# transboard.net
KiCad netlist of a schematic drawn in Altium Designer
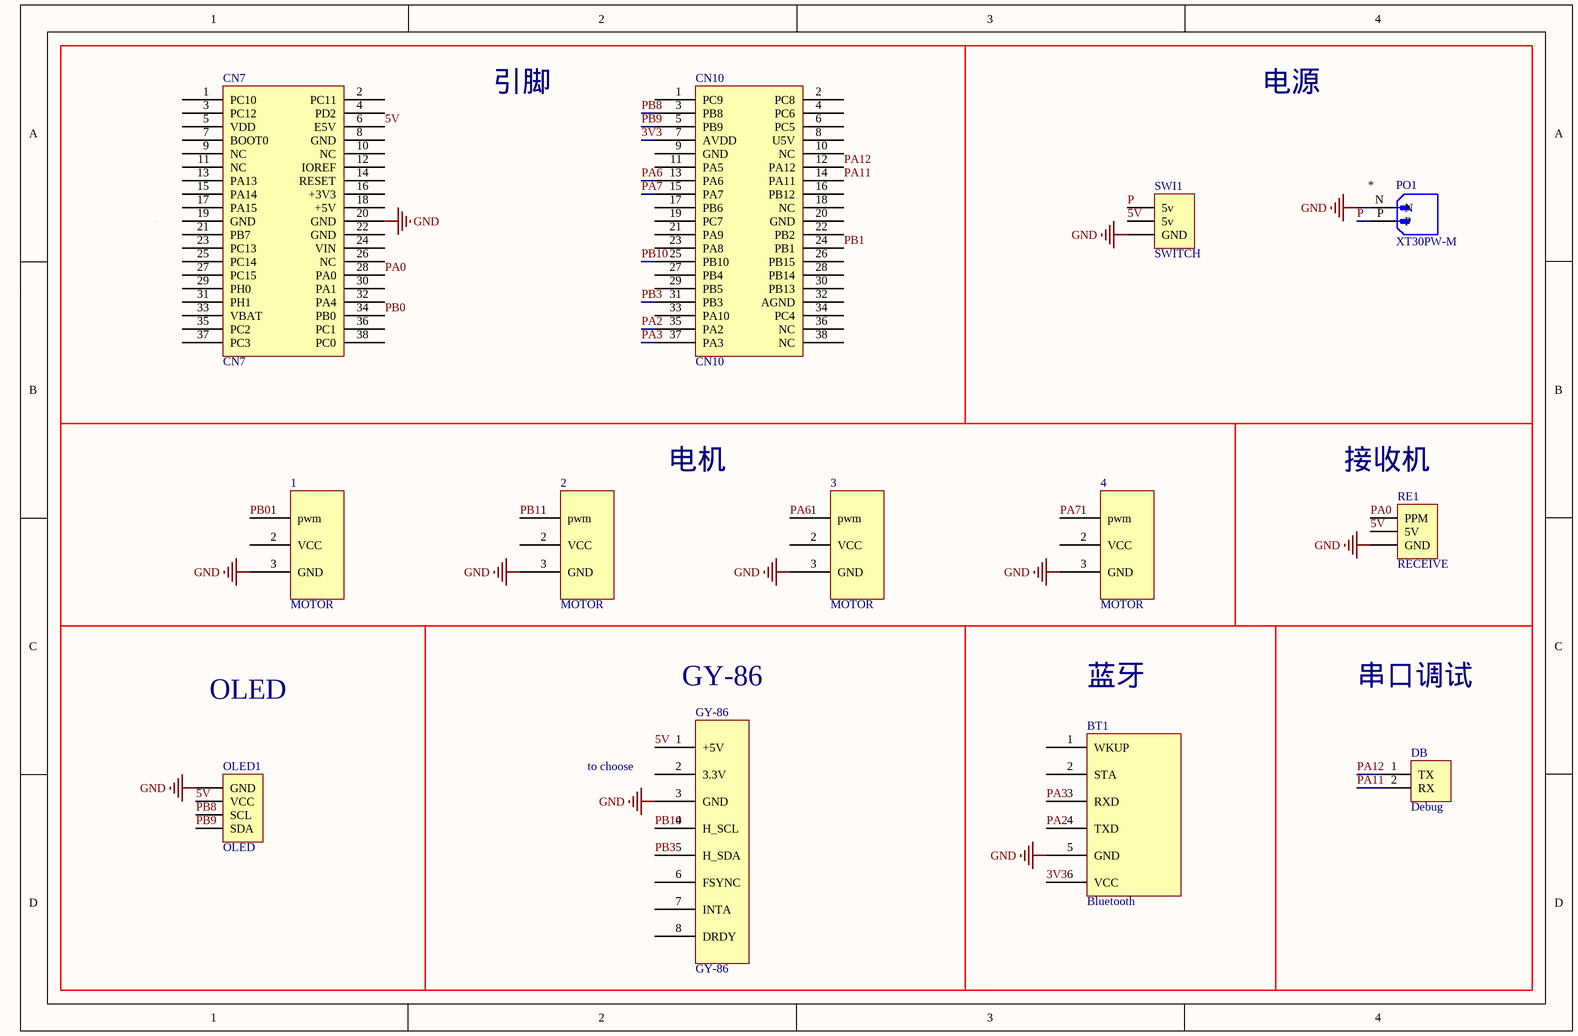
[diagram p0: transboard.SchDoc]

(export (version "E")
  (design (tool "Eeschema 10.0.6"))
  (components
    (comp (ref "1") (value "MOTOR") (footprint "M") (libsource (lib "Free Documents") (part "M")))
    (comp (ref "2") (value "MOTOR") (footprint "M") (libsource (lib "Free Documents") (part "M")))
    (comp (ref "3") (value "MOTOR") (footprint "M") (libsource (lib "Free Documents") (part "M")))
    (comp (ref "4") (value "MOTOR") (footprint "M") (libsource (lib "Free Documents") (part "M")))
    (comp (ref "BT1")
      (value "Bluetooth")
      (footprint "Bluetooth")
      (libsource (lib "Free Documents") (part "Bluetooth"))
    )
    (comp (ref "CN7") (value "CN7") (footprint "CN7") (libsource (lib "Free Documents") (part "CN7")))
    (comp (ref "CN10") (value "CN10") (footprint "CN10") (libsource (lib "Free Documents") (part "CN10")))
    (comp (ref "DB")
      (value "Debug")
      (footprint "HDR1X2")
      (description "Header, 2-Pin")
      (fields (field (name "PUBLISHER") "Altium Limited"))
      (libsource (lib "Miscellaneous Connectors") (part "Header 2"))
    )
    (comp (ref "GY-86") (value "GY-86") (footprint "HDR1X8") (libsource (lib "转接板lib") (part "GY-86")))
    (comp (ref "OLED1")
      (value "OLED")
      (footprint "HDR1X4")
      (description "Header, 4-Pin")
      (fields (field (name "PUBLISHER") "Altium Limited"))
      (libsource (lib "Free Documents") (part "Header 4"))
    )
    (comp (ref "PO1")
      (value "XT30PW-M")
      (footprint "AMASS_XT30PW-M")
      (description "Socket; DC supply; XT30; male; PIN: 2; on PCBs; THT; Colour: yellow")
      (fields (field (name "MF") "AMASS") (field (name "ALTIUM_VALUE") "*"))
      (libsource (lib "Free Documents") (part "XT30PW-M"))
    )
    (comp (ref "RE1")
      (value "RECEIVE")
      (footprint "HDR1X3")
      (description "Header, 3-Pin")
      (fields (field (name "PUBLISHER") "Altium Limited"))
      (libsource (lib "Free Documents") (part "Header 3"))
    )
    (comp (ref "SWI1")
      (value "SWITCH")
      (footprint "HDR1X3")
      (description "Header, 3-Pin")
      (fields (field (name "PUBLISHER") "Altium Limited"))
      (libsource (lib "Free Documents") (part "Header 3_1"))
    )
  )
  (nets
    (net (code "1") (name "/3V3") (class "Default")
      (node (ref "BT1") (pin "6") (pinfunction "VCC_6") (pintype "passive"))
      (node (ref "CN10") (pin "7") (pinfunction "AVDD_7") (pintype "passive"))
    )
    (net (code "2") (name "/5V") (class "Default")
      (node (ref "CN7") (pin "6") (pinfunction "E5V_6") (pintype "passive"))
      (node (ref "GY-86") (pin "1") (pinfunction "+5V_1") (pintype "passive"))
      (node (ref "OLED1") (pin "2") (pinfunction "VCC_2") (pintype "passive"))
      (node (ref "RE1") (pin "2") (pinfunction "5V_2") (pintype "passive"))
      (node (ref "SWI1") (pin "2") (pinfunction "5v_2") (pintype "passive"))
    )
    (net (code "4") (name "/P") (class "Default")
      (node (ref "PO1") (pin "P") (pinfunction "P_P") (pintype "power_in"))
      (node (ref "SWI1") (pin "1") (pinfunction "5v_1") (pintype "passive"))
    )
    (net (code "5") (name "/PA0") (class "Default")
      (node (ref "CN7") (pin "28") (pinfunction "PA0_28") (pintype "passive"))
      (node (ref "RE1") (pin "1") (pinfunction "PPM_1") (pintype "passive"))
    )
    (net (code "6") (name "/PA2") (class "Default")
      (node (ref "BT1") (pin "4") (pinfunction "TXD_4") (pintype "passive"))
      (node (ref "CN10") (pin "35") (pinfunction "PA2_35") (pintype "passive"))
    )
    (net (code "7") (name "/PA3") (class "Default")
      (node (ref "BT1") (pin "3") (pinfunction "RXD_3") (pintype "passive"))
      (node (ref "CN10") (pin "37") (pinfunction "PA3_37") (pintype "passive"))
    )
    (net (code "8") (name "/PA6") (class "Default")
      (node (ref "3") (pin "1") (pinfunction "pwm_1") (pintype "passive"))
      (node (ref "CN10") (pin "13") (pinfunction "PA6_13") (pintype "passive"))
    )
    (net (code "9") (name "/PA7") (class "Default")
      (node (ref "4") (pin "1") (pinfunction "pwm_1") (pintype "passive"))
      (node (ref "CN10") (pin "15") (pinfunction "PA7_15") (pintype "passive"))
    )
    (net (code "10") (name "/PA11") (class "Default")
      (node (ref "CN10") (pin "14") (pinfunction "PA11_14") (pintype "passive"))
      (node (ref "DB") (pin "2") (pinfunction "RX_2") (pintype "passive"))
    )
    (net (code "11") (name "/PA12") (class "Default")
      (node (ref "CN10") (pin "12") (pinfunction "PA12_12") (pintype "passive"))
      (node (ref "DB") (pin "1") (pinfunction "TX_1") (pintype "passive"))
    )
    (net (code "12") (name "/PB0") (class "Default")
      (node (ref "1") (pin "1") (pinfunction "pwm_1") (pintype "passive"))
      (node (ref "CN7") (pin "34") (pinfunction "PB0_34") (pintype "passive"))
    )
    (net (code "13") (name "/PB1") (class "Default")
      (node (ref "2") (pin "1") (pinfunction "pwm_1") (pintype "passive"))
      (node (ref "CN10") (pin "24") (pinfunction "PB1_24") (pintype "passive"))
    )
    (net (code "14") (name "/PB3") (class "Default")
      (node (ref "CN10") (pin "31") (pinfunction "PB3_31") (pintype "passive"))
      (node (ref "GY-86") (pin "5") (pinfunction "H_SDA_5") (pintype "passive"))
    )
    (net (code "15") (name "/PB8") (class "Default")
      (node (ref "CN10") (pin "3") (pinfunction "PB8_3") (pintype "passive"))
      (node (ref "OLED1") (pin "3") (pinfunction "SCL_3") (pintype "passive"))
    )
    (net (code "16") (name "/PB9") (class "Default")
      (node (ref "CN10") (pin "5") (pinfunction "PB9_5") (pintype "passive"))
      (node (ref "OLED1") (pin "4") (pinfunction "SDA_4") (pintype "passive"))
    )
    (net (code "17") (name "/PB10") (class "Default")
      (node (ref "CN10") (pin "25") (pinfunction "PB10_25") (pintype "passive"))
      (node (ref "GY-86") (pin "4") (pinfunction "H_SCL_4") (pintype "passive"))
    )
    (net (code "18") (name "GND") (class "Default")
      (node (ref "1") (pin "3") (pinfunction "GND_3") (pintype "passive"))
      (node (ref "2") (pin "3") (pinfunction "GND_3") (pintype "passive"))
      (node (ref "3") (pin "3") (pinfunction "GND_3") (pintype "passive"))
      (node (ref "4") (pin "3") (pinfunction "GND_3") (pintype "passive"))
      (node (ref "BT1") (pin "5") (pinfunction "GND_5") (pintype "passive"))
      (node (ref "CN7") (pin "20") (pinfunction "GND_20") (pintype "passive"))
      (node (ref "GY-86") (pin "3") (pinfunction "GND_3") (pintype "passive"))
      (node (ref "OLED1") (pin "1") (pinfunction "GND_1") (pintype "passive"))
      (node (ref "PO1") (pin "N") (pinfunction "N_N") (pintype "power_in"))
      (node (ref "RE1") (pin "3") (pinfunction "GND_3") (pintype "passive"))
      (node (ref "SWI1") (pin "3") (pinfunction "GND_3") (pintype "passive"))
    )
    (net (code "19") (name "unconnected-(1-VCC-Pad2)") (class "Default")
      (node (ref "1") (pin "2") (pinfunction "VCC_2") (pintype "passive"))
    )
    (net (code "20") (name "unconnected-(2-VCC-Pad2)") (class "Default")
      (node (ref "2") (pin "2") (pinfunction "VCC_2") (pintype "passive"))
    )
    (net (code "21") (name "unconnected-(3-VCC-Pad2)") (class "Default")
      (node (ref "3") (pin "2") (pinfunction "VCC_2") (pintype "passive"))
    )
    (net (code "22") (name "unconnected-(4-VCC-Pad2)") (class "Default")
      (node (ref "4") (pin "2") (pinfunction "VCC_2") (pintype "passive"))
    )
    (net (code "23") (name "unconnected-(BT1-STA-Pad2)") (class "Default")
      (node (ref "BT1") (pin "2") (pinfunction "STA_2") (pintype "passive"))
    )
    (net (code "24") (name "unconnected-(BT1-WKUP-Pad1)") (class "Default")
      (node (ref "BT1") (pin "1") (pinfunction "WKUP_1") (pintype "passive"))
    )
    (net (code "25") (name "unconnected-(CN7-+3V3-Pad16)") (class "Default")
      (node (ref "CN7") (pin "16") (pinfunction "+3V3_16") (pintype "passive"))
    )
    (net (code "26") (name "unconnected-(CN7-+5V-Pad18)") (class "Default")
      (node (ref "CN7") (pin "18") (pinfunction "+5V_18") (pintype "passive"))
    )
    (net (code "27") (name "unconnected-(CN7-BOOT0-Pad7)") (class "Default")
      (node (ref "CN7") (pin "7") (pinfunction "BOOT0_7") (pintype "passive"))
    )
    (net (code "28") (name "unconnected-(CN7-GND-Pad8)") (class "Default")
      (node (ref "CN7") (pin "8") (pinfunction "GND_8") (pintype "passive"))
    )
    (net (code "29") (name "unconnected-(CN7-GND-Pad19)") (class "Default")
      (node (ref "CN7") (pin "19") (pinfunction "GND_19") (pintype "passive"))
    )
    (net (code "30") (name "unconnected-(CN7-GND-Pad22)") (class "Default")
      (node (ref "CN7") (pin "22") (pinfunction "GND_22") (pintype "passive"))
    )
    (net (code "31") (name "unconnected-(CN7-IOREF-Pad12)") (class "Default")
      (node (ref "CN7") (pin "12") (pinfunction "IOREF_12") (pintype "passive"))
    )
    (net (code "32") (name "unconnected-(CN7-NC-Pad9)") (class "Default")
      (node (ref "CN7") (pin "9") (pinfunction "NC_9") (pintype "passive"))
    )
    (net (code "33") (name "unconnected-(CN7-NC-Pad10)") (class "Default")
      (node (ref "CN7") (pin "10") (pinfunction "NC_10") (pintype "passive"))
    )
    (net (code "34") (name "unconnected-(CN7-NC-Pad11)") (class "Default")
      (node (ref "CN7") (pin "11") (pinfunction "NC_11") (pintype "passive"))
    )
    (net (code "35") (name "unconnected-(CN7-NC-Pad26)") (class "Default")
      (node (ref "CN7") (pin "26") (pinfunction "NC_26") (pintype "passive"))
    )
    (net (code "36") (name "unconnected-(CN7-PA1-Pad30)") (class "Default")
      (node (ref "CN7") (pin "30") (pinfunction "PA1_30") (pintype "passive"))
    )
    (net (code "37") (name "unconnected-(CN7-PA4-Pad32)") (class "Default")
      (node (ref "CN7") (pin "32") (pinfunction "PA4_32") (pintype "passive"))
    )
    (net (code "38") (name "unconnected-(CN7-PA13-Pad13)") (class "Default")
      (node (ref "CN7") (pin "13") (pinfunction "PA13_13") (pintype "passive"))
    )
    (net (code "39") (name "unconnected-(CN7-PA14-Pad15)") (class "Default")
      (node (ref "CN7") (pin "15") (pinfunction "PA14_15") (pintype "passive"))
    )
    (net (code "40") (name "unconnected-(CN7-PA15-Pad17)") (class "Default")
      (node (ref "CN7") (pin "17") (pinfunction "PA15_17") (pintype "passive"))
    )
    (net (code "41") (name "unconnected-(CN7-PB7-Pad21)") (class "Default")
      (node (ref "CN7") (pin "21") (pinfunction "PB7_21") (pintype "passive"))
    )
    (net (code "42") (name "unconnected-(CN7-PC0-Pad38)") (class "Default")
      (node (ref "CN7") (pin "38") (pinfunction "PC0_38") (pintype "passive"))
    )
    (net (code "43") (name "unconnected-(CN7-PC1-Pad36)") (class "Default")
      (node (ref "CN7") (pin "36") (pinfunction "PC1_36") (pintype "passive"))
    )
    (net (code "44") (name "unconnected-(CN7-PC2-Pad35)") (class "Default")
      (node (ref "CN7") (pin "35") (pinfunction "PC2_35") (pintype "passive"))
    )
    (net (code "45") (name "unconnected-(CN7-PC3-Pad37)") (class "Default")
      (node (ref "CN7") (pin "37") (pinfunction "PC3_37") (pintype "passive"))
    )
    (net (code "46") (name "unconnected-(CN7-PC10-Pad1)") (class "Default")
      (node (ref "CN7") (pin "1") (pinfunction "PC10_1") (pintype "passive"))
    )
    (net (code "47") (name "unconnected-(CN7-PC11-Pad2)") (class "Default")
      (node (ref "CN7") (pin "2") (pinfunction "PC11_2") (pintype "passive"))
    )
    (net (code "48") (name "unconnected-(CN7-PC12-Pad3)") (class "Default")
      (node (ref "CN7") (pin "3") (pinfunction "PC12_3") (pintype "passive"))
    )
    (net (code "49") (name "unconnected-(CN7-PC13-Pad23)") (class "Default")
      (node (ref "CN7") (pin "23") (pinfunction "PC13_23") (pintype "passive"))
    )
    (net (code "50") (name "unconnected-(CN7-PC14-Pad25)") (class "Default")
      (node (ref "CN7") (pin "25") (pinfunction "PC14_25") (pintype "passive"))
    )
    (net (code "51") (name "unconnected-(CN7-PC15-Pad27)") (class "Default")
      (node (ref "CN7") (pin "27") (pinfunction "PC15_27") (pintype "passive"))
    )
    (net (code "52") (name "unconnected-(CN7-PD2-Pad4)") (class "Default")
      (node (ref "CN7") (pin "4") (pinfunction "PD2_4") (pintype "passive"))
    )
    (net (code "53") (name "unconnected-(CN7-PH0-Pad29)") (class "Default")
      (node (ref "CN7") (pin "29") (pinfunction "PH0_29") (pintype "passive"))
    )
    (net (code "54") (name "unconnected-(CN7-PH1-Pad31)") (class "Default")
      (node (ref "CN7") (pin "31") (pinfunction "PH1_31") (pintype "passive"))
    )
    (net (code "55") (name "unconnected-(CN7-RESET-Pad14)") (class "Default")
      (node (ref "CN7") (pin "14") (pinfunction "RESET_14") (pintype "passive"))
    )
    (net (code "56") (name "unconnected-(CN7-VBAT-Pad33)") (class "Default")
      (node (ref "CN7") (pin "33") (pinfunction "VBAT_33") (pintype "passive"))
    )
    (net (code "57") (name "unconnected-(CN7-VDD-Pad5)") (class "Default")
      (node (ref "CN7") (pin "5") (pinfunction "VDD_5") (pintype "passive"))
    )
    (net (code "58") (name "unconnected-(CN7-VIN-Pad24)") (class "Default")
      (node (ref "CN7") (pin "24") (pinfunction "VIN_24") (pintype "passive"))
    )
    (net (code "59") (name "unconnected-(CN10-AGND-Pad32)") (class "Default")
      (node (ref "CN10") (pin "32") (pinfunction "AGND_32") (pintype "passive"))
    )
    (net (code "60") (name "unconnected-(CN10-GND-Pad9)") (class "Default")
      (node (ref "CN10") (pin "9") (pinfunction "GND_9") (pintype "passive"))
    )
    (net (code "61") (name "unconnected-(CN10-GND-Pad20)") (class "Default")
      (node (ref "CN10") (pin "20") (pinfunction "GND_20") (pintype "passive"))
    )
    (net (code "62") (name "unconnected-(CN10-NC-Pad10)") (class "Default")
      (node (ref "CN10") (pin "10") (pinfunction "NC_10") (pintype "passive"))
    )
    (net (code "63") (name "unconnected-(CN10-NC-Pad18)") (class "Default")
      (node (ref "CN10") (pin "18") (pinfunction "NC_18") (pintype "passive"))
    )
    (net (code "64") (name "unconnected-(CN10-NC-Pad36)") (class "Default")
      (node (ref "CN10") (pin "36") (pinfunction "NC_36") (pintype "passive"))
    )
    (net (code "65") (name "unconnected-(CN10-NC-Pad38)") (class "Default")
      (node (ref "CN10") (pin "38") (pinfunction "NC_38") (pintype "passive"))
    )
    (net (code "66") (name "unconnected-(CN10-PA5-Pad11)") (class "Default")
      (node (ref "CN10") (pin "11") (pinfunction "PA5_11") (pintype "passive"))
    )
    (net (code "67") (name "unconnected-(CN10-PA8-Pad23)") (class "Default")
      (node (ref "CN10") (pin "23") (pinfunction "PA8_23") (pintype "passive"))
    )
    (net (code "68") (name "unconnected-(CN10-PA9-Pad21)") (class "Default")
      (node (ref "CN10") (pin "21") (pinfunction "PA9_21") (pintype "passive"))
    )
    (net (code "69") (name "unconnected-(CN10-PA10-Pad33)") (class "Default")
      (node (ref "CN10") (pin "33") (pinfunction "PA10_33") (pintype "passive"))
    )
    (net (code "70") (name "unconnected-(CN10-PB2-Pad22)") (class "Default")
      (node (ref "CN10") (pin "22") (pinfunction "PB2_22") (pintype "passive"))
    )
    (net (code "71") (name "unconnected-(CN10-PB4-Pad27)") (class "Default")
      (node (ref "CN10") (pin "27") (pinfunction "PB4_27") (pintype "passive"))
    )
    (net (code "72") (name "unconnected-(CN10-PB5-Pad29)") (class "Default")
      (node (ref "CN10") (pin "29") (pinfunction "PB5_29") (pintype "passive"))
    )
    (net (code "73") (name "unconnected-(CN10-PB6-Pad17)") (class "Default")
      (node (ref "CN10") (pin "17") (pinfunction "PB6_17") (pintype "passive"))
    )
    (net (code "74") (name "unconnected-(CN10-PB12-Pad16)") (class "Default")
      (node (ref "CN10") (pin "16") (pinfunction "PB12_16") (pintype "passive"))
    )
    (net (code "75") (name "unconnected-(CN10-PB13-Pad30)") (class "Default")
      (node (ref "CN10") (pin "30") (pinfunction "PB13_30") (pintype "passive"))
    )
    (net (code "76") (name "unconnected-(CN10-PB14-Pad28)") (class "Default")
      (node (ref "CN10") (pin "28") (pinfunction "PB14_28") (pintype "passive"))
    )
    (net (code "77") (name "unconnected-(CN10-PB15-Pad26)") (class "Default")
      (node (ref "CN10") (pin "26") (pinfunction "PB15_26") (pintype "passive"))
    )
    (net (code "78") (name "unconnected-(CN10-PC4-Pad34)") (class "Default")
      (node (ref "CN10") (pin "34") (pinfunction "PC4_34") (pintype "passive"))
    )
    (net (code "79") (name "unconnected-(CN10-PC5-Pad6)") (class "Default")
      (node (ref "CN10") (pin "6") (pinfunction "PC5_6") (pintype "passive"))
    )
    (net (code "80") (name "unconnected-(CN10-PC6-Pad4)") (class "Default")
      (node (ref "CN10") (pin "4") (pinfunction "PC6_4") (pintype "passive"))
    )
    (net (code "81") (name "unconnected-(CN10-PC7-Pad19)") (class "Default")
      (node (ref "CN10") (pin "19") (pinfunction "PC7_19") (pintype "passive"))
    )
    (net (code "82") (name "unconnected-(CN10-PC8-Pad2)") (class "Default")
      (node (ref "CN10") (pin "2") (pinfunction "PC8_2") (pintype "passive"))
    )
    (net (code "83") (name "unconnected-(CN10-PC9-Pad1)") (class "Default")
      (node (ref "CN10") (pin "1") (pinfunction "PC9_1") (pintype "passive"))
    )
    (net (code "84") (name "unconnected-(CN10-U5V-Pad8)") (class "Default")
      (node (ref "CN10") (pin "8") (pinfunction "U5V_8") (pintype "passive"))
    )
    (net (code "85") (name "unconnected-(GY-86-3.3V-Pad2)") (class "Default")
      (node (ref "GY-86") (pin "2") (pinfunction "3.3V_2") (pintype "passive"))
    )
    (net (code "86") (name "unconnected-(GY-86-DRDY-Pad8)") (class "Default")
      (node (ref "GY-86") (pin "8") (pinfunction "DRDY_8") (pintype "passive"))
    )
    (net (code "87") (name "unconnected-(GY-86-FSYNC-Pad6)") (class "Default")
      (node (ref "GY-86") (pin "6") (pinfunction "FSYNC_6") (pintype "passive"))
    )
    (net (code "88") (name "unconnected-(GY-86-INTA-Pad7)") (class "Default")
      (node (ref "GY-86") (pin "7") (pinfunction "INTA_7") (pintype "passive"))
    )
  )
)
